# AMS_Slave_Measurement.net
KiCad netlist of a schematic drawn in Altium Designer
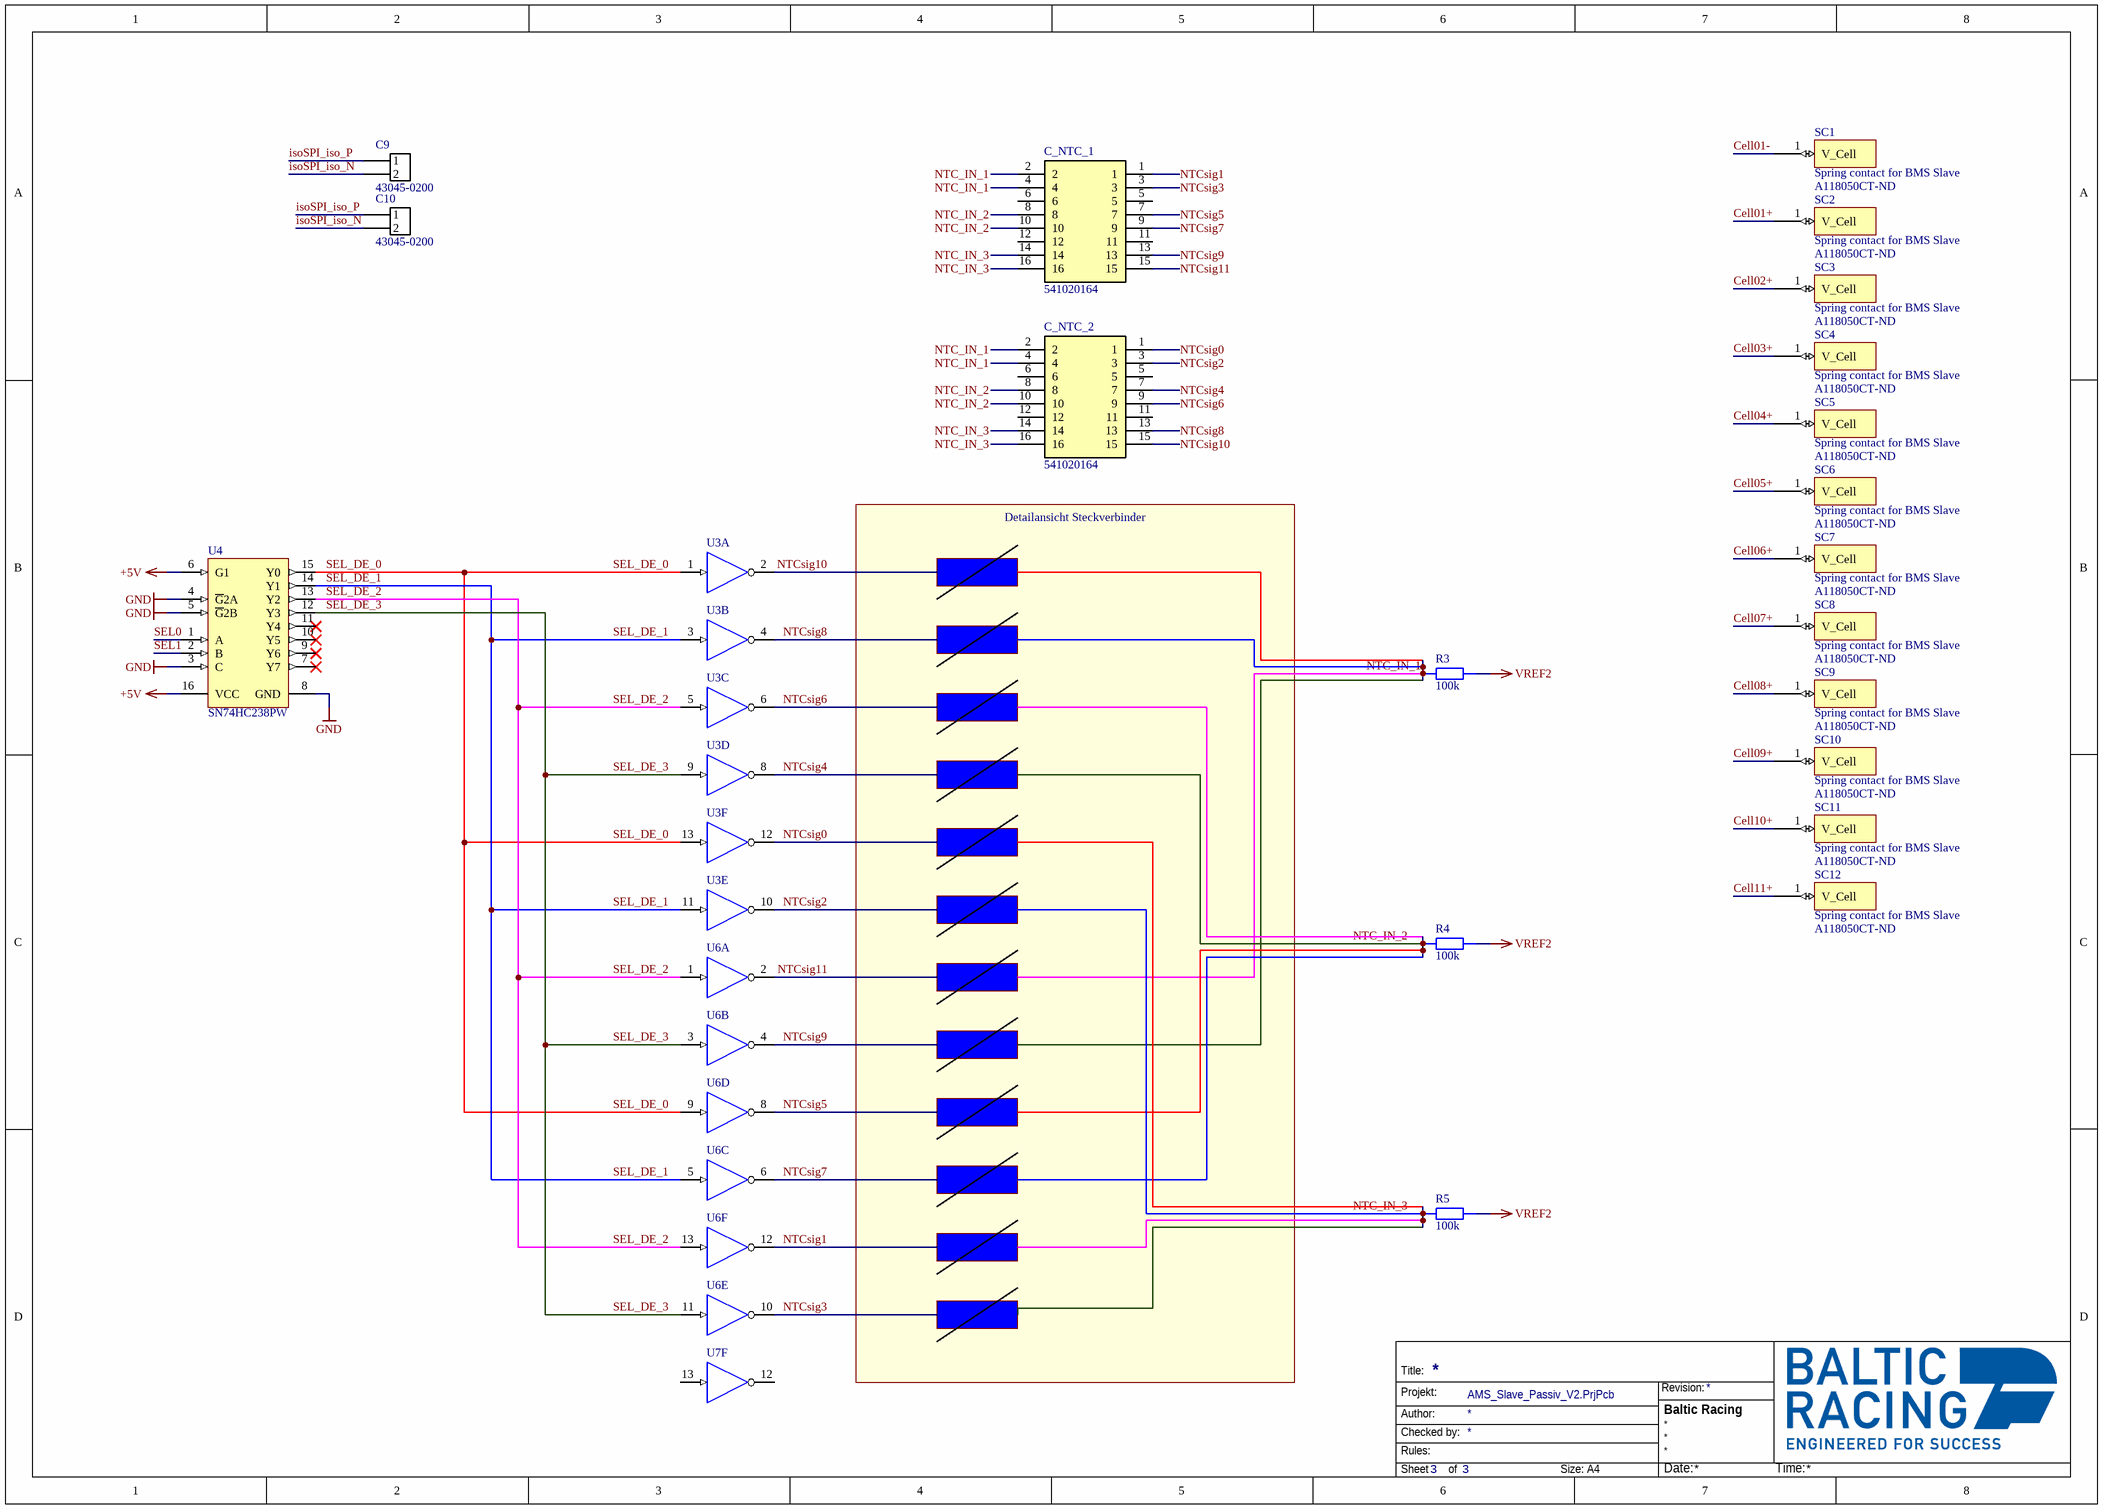
[diagram p0: AMS_Slave_Measurement.SchDoc]

(export (version "E")
  (design (tool "Eeschema 10.0.6"))
  (components
    (comp (ref "C9")
      (value "43045-0200")
      (footprint "43650-0200")
      (description "Molex Micro-Fit 3.0 2-Pin\r\n600V\r\n8.5A")
      (libsource (lib "Standardbauteile") (part "MicroFit3.0 2-Pin"))
    )
    (comp (ref "C10")
      (value "43045-0200")
      (footprint "43650-0200")
      (description "Molex Micro-Fit 3.0 2-Pin\r\n600V\r\n8.5A")
      (libsource (lib "Standardbauteile") (part "MicroFit3.0 2-Pin"))
    )
    (comp (ref "C_NTC_1")
      (value "541020164")
      (footprint "541020164")
      (libsource (lib "libNico") (part "541020164"))
    )
    (comp (ref "C_NTC_2")
      (value "541020164")
      (footprint "541020164")
      (libsource (lib "libNico") (part "541020164"))
    )
    (comp (ref "R3")
      (value "100k")
      (footprint "STACKPOLE CSR0603")
      (description "Resistor with multiple footprints")
      (fields (field (name "Comment") "SMD Resistor"))
      (libsource (lib "Standardbauteile") (part "SMD Resistor"))
    )
    (comp (ref "R4")
      (value "100k")
      (footprint "STACKPOLE CSR0603")
      (description "Resistor with multiple footprints")
      (fields (field (name "Comment") "SMD Resistor"))
      (libsource (lib "Standardbauteile") (part "SMD Resistor"))
    )
    (comp (ref "R5")
      (value "100k")
      (footprint "STACKPOLE CSR0603")
      (description "Resistor with multiple footprints")
      (fields (field (name "Comment") "SMD Resistor"))
      (libsource (lib "Standardbauteile") (part "SMD Resistor"))
    )
    (comp (ref "SC1")
      (value "Spring contact for BMS Slave")
      (footprint "1734300-1 Spring Contact")
      (fields (field (name "SUPPLIER PART NUMBER 1") "A118050CT-ND"))
      (libsource (lib "Integrated_LibraryLukas") (part "1734300-1"))
    )
    (comp (ref "SC2")
      (value "Spring contact for BMS Slave")
      (footprint "1734300-1 Spring Contact")
      (fields (field (name "SUPPLIER PART NUMBER 1") "A118050CT-ND"))
      (libsource (lib "Integrated_LibraryLukas") (part "1734300-1"))
    )
    (comp (ref "SC3")
      (value "Spring contact for BMS Slave")
      (footprint "1734300-1 Spring Contact")
      (fields (field (name "SUPPLIER PART NUMBER 1") "A118050CT-ND"))
      (libsource (lib "Integrated_LibraryLukas") (part "1734300-1"))
    )
    (comp (ref "SC4")
      (value "Spring contact for BMS Slave")
      (footprint "1734300-1 Spring Contact")
      (fields (field (name "SUPPLIER PART NUMBER 1") "A118050CT-ND"))
      (libsource (lib "Integrated_LibraryLukas") (part "1734300-1"))
    )
    (comp (ref "SC5")
      (value "Spring contact for BMS Slave")
      (footprint "1734300-1 Spring Contact")
      (fields (field (name "SUPPLIER PART NUMBER 1") "A118050CT-ND"))
      (libsource (lib "Integrated_LibraryLukas") (part "1734300-1"))
    )
    (comp (ref "SC6")
      (value "Spring contact for BMS Slave")
      (footprint "1734300-1 Spring Contact")
      (fields (field (name "SUPPLIER PART NUMBER 1") "A118050CT-ND"))
      (libsource (lib "Integrated_LibraryLukas") (part "1734300-1"))
    )
    (comp (ref "SC7")
      (value "Spring contact for BMS Slave")
      (footprint "1734300-1 Spring Contact")
      (fields (field (name "SUPPLIER PART NUMBER 1") "A118050CT-ND"))
      (libsource (lib "Integrated_LibraryLukas") (part "1734300-1"))
    )
    (comp (ref "SC8")
      (value "Spring contact for BMS Slave")
      (footprint "1734300-1 Spring Contact")
      (fields (field (name "SUPPLIER PART NUMBER 1") "A118050CT-ND"))
      (libsource (lib "Integrated_LibraryLukas") (part "1734300-1"))
    )
    (comp (ref "SC9")
      (value "Spring contact for BMS Slave")
      (footprint "1734300-1 Spring Contact")
      (fields (field (name "SUPPLIER PART NUMBER 1") "A118050CT-ND"))
      (libsource (lib "Integrated_LibraryLukas") (part "1734300-1"))
    )
    (comp (ref "SC10")
      (value "Spring contact for BMS Slave")
      (footprint "1734300-1 Spring Contact")
      (fields (field (name "SUPPLIER PART NUMBER 1") "A118050CT-ND"))
      (libsource (lib "Integrated_LibraryLukas") (part "1734300-1"))
    )
    (comp (ref "SC11")
      (value "Spring contact for BMS Slave")
      (footprint "1734300-1 Spring Contact")
      (fields (field (name "SUPPLIER PART NUMBER 1") "A118050CT-ND"))
      (libsource (lib "Integrated_LibraryLukas") (part "1734300-1"))
    )
    (comp (ref "SC12")
      (value "Spring contact for BMS Slave")
      (footprint "1734300-1 Spring Contact")
      (fields (field (name "SUPPLIER PART NUMBER 1") "A118050CT-ND"))
      (libsource (lib "Integrated_LibraryLukas") (part "1734300-1"))
    )
    (comp (ref "U3")
      (value "SN74LVC06APWR")
      (footprint "PW0014A_M")
      (description "Hex Inverter Buffers/Drivers With Open-Drain Outputs, PW0014A, LARGE T&R")
      (fields
        (field (name "GENERIC PART NUMBER") "SN74LVC06A")
        (field (name "MANUFACTURER") "Texas Instruments")
      )
      (libsource (lib "Altium Content Vault") (part "TI-CD_SNX4XXXXX05X_X6X-14"))
    )
    (comp (ref "U4")
      (value "SN74HC238PW")
      (footprint "SN74HC238PW Footprint")
      (libsource (lib "Integrated_LibraryLukas_New") (part "SN74HC238PW"))
    )
    (comp (ref "U6")
      (value "SN74LVC06APWR")
      (footprint "PW0014A_M")
      (description "Hex Inverter Buffers/Drivers With Open-Drain Outputs, PW0014A, LARGE T&R")
      (fields
        (field (name "GENERIC PART NUMBER") "SN74LVC06A")
        (field (name "MANUFACTURER") "Texas Instruments")
      )
      (libsource (lib "Altium Content Vault") (part "TI-CD_SNX4XXXXX05X_X6X-14"))
    )
    (comp (ref "U7")
      (value "SN74LVC06APWR")
      (footprint "PW0014A_M")
      (description "Hex Inverter Buffers/Drivers With Open-Drain Outputs, PW0014A, LARGE T&R")
      (fields
        (field (name "GENERIC PART NUMBER") "SN74LVC06A")
        (field (name "MANUFACTURER") "Texas Instruments")
      )
      (libsource (lib "Altium Content Vault") (part "TI-CD_SNX4XXXXX05X_X6X-14"))
    )
  )
  (nets
    (net (code "1") (name "+5V") (class "Default")
      (node (ref "U4") (pin "16") (pinfunction "VCC_16") (pintype "power_in"))
      (node (ref "U4") (pin "6") (pinfunction "G1_6") (pintype "input"))
    )
    (net (code "2") (name "/Cell01+") (class "Default")
      (node (ref "SC2") (pin "1") (pinfunction "V_Cell_1") (pintype "bidirectional"))
    )
    (net (code "3") (name "/Cell01-") (class "Default")
      (node (ref "SC1") (pin "1") (pinfunction "V_Cell_1") (pintype "bidirectional"))
    )
    (net (code "4") (name "/Cell02+") (class "Default")
      (node (ref "SC3") (pin "1") (pinfunction "V_Cell_1") (pintype "bidirectional"))
    )
    (net (code "5") (name "/Cell03+") (class "Default")
      (node (ref "SC4") (pin "1") (pinfunction "V_Cell_1") (pintype "bidirectional"))
    )
    (net (code "6") (name "/Cell04+") (class "Default")
      (node (ref "SC5") (pin "1") (pinfunction "V_Cell_1") (pintype "bidirectional"))
    )
    (net (code "7") (name "/Cell05+") (class "Default")
      (node (ref "SC6") (pin "1") (pinfunction "V_Cell_1") (pintype "bidirectional"))
    )
    (net (code "8") (name "/Cell06+") (class "Default")
      (node (ref "SC7") (pin "1") (pinfunction "V_Cell_1") (pintype "bidirectional"))
    )
    (net (code "9") (name "/Cell07+") (class "Default")
      (node (ref "SC8") (pin "1") (pinfunction "V_Cell_1") (pintype "bidirectional"))
    )
    (net (code "10") (name "/Cell08+") (class "Default")
      (node (ref "SC9") (pin "1") (pinfunction "V_Cell_1") (pintype "bidirectional"))
    )
    (net (code "11") (name "/Cell09+") (class "Default")
      (node (ref "SC10") (pin "1") (pinfunction "V_Cell_1") (pintype "bidirectional"))
    )
    (net (code "12") (name "/Cell10+") (class "Default")
      (node (ref "SC11") (pin "1") (pinfunction "V_Cell_1") (pintype "bidirectional"))
    )
    (net (code "13") (name "/Cell11+") (class "Default")
      (node (ref "SC12") (pin "1") (pinfunction "V_Cell_1") (pintype "bidirectional"))
    )
    (net (code "14") (name "/NTC_IN_1") (class "Default")
      (node (ref "C_NTC_1") (pin "2") (pinfunction "2_2") (pintype "passive"))
      (node (ref "C_NTC_1") (pin "4") (pinfunction "4_4") (pintype "passive"))
      (node (ref "C_NTC_2") (pin "2") (pinfunction "2_2") (pintype "passive"))
      (node (ref "C_NTC_2") (pin "4") (pinfunction "4_4") (pintype "passive"))
      (node (ref "R3") (pin "1") (pinfunction "1_1") (pintype "passive"))
    )
    (net (code "15") (name "/NTC_IN_2") (class "Default")
      (node (ref "C_NTC_1") (pin "10") (pinfunction "10_10") (pintype "passive"))
      (node (ref "C_NTC_1") (pin "8") (pinfunction "8_8") (pintype "passive"))
      (node (ref "C_NTC_2") (pin "10") (pinfunction "10_10") (pintype "passive"))
      (node (ref "C_NTC_2") (pin "8") (pinfunction "8_8") (pintype "passive"))
      (node (ref "R4") (pin "1") (pinfunction "1_1") (pintype "passive"))
    )
    (net (code "16") (name "/NTC_IN_3") (class "Default")
      (node (ref "C_NTC_1") (pin "14") (pinfunction "14_14") (pintype "passive"))
      (node (ref "C_NTC_1") (pin "16") (pinfunction "16_16") (pintype "passive"))
      (node (ref "C_NTC_2") (pin "14") (pinfunction "14_14") (pintype "passive"))
      (node (ref "C_NTC_2") (pin "16") (pinfunction "16_16") (pintype "passive"))
      (node (ref "R5") (pin "1") (pinfunction "1_1") (pintype "passive"))
    )
    (net (code "17") (name "/NTCsig0") (class "Default")
      (node (ref "C_NTC_2") (pin "1") (pinfunction "1_1") (pintype "passive"))
      (node (ref "U3") (pin "12") (pinfunction "~{6Y}_12") (pintype "open_collector"))
    )
    (net (code "18") (name "/NTCsig1") (class "Default")
      (node (ref "C_NTC_1") (pin "1") (pinfunction "1_1") (pintype "passive"))
      (node (ref "U6") (pin "12") (pinfunction "~{6Y}_12") (pintype "open_collector"))
    )
    (net (code "19") (name "/NTCsig2") (class "Default")
      (node (ref "C_NTC_2") (pin "3") (pinfunction "3_3") (pintype "passive"))
      (node (ref "U3") (pin "10") (pinfunction "~{5Y}_10") (pintype "open_collector"))
    )
    (net (code "20") (name "/NTCsig3") (class "Default")
      (node (ref "C_NTC_1") (pin "3") (pinfunction "3_3") (pintype "passive"))
      (node (ref "U6") (pin "10") (pinfunction "~{5Y}_10") (pintype "open_collector"))
    )
    (net (code "21") (name "/NTCsig4") (class "Default")
      (node (ref "C_NTC_2") (pin "7") (pinfunction "7_7") (pintype "passive"))
      (node (ref "U3") (pin "8") (pinfunction "~{4Y}_8") (pintype "open_collector"))
    )
    (net (code "22") (name "/NTCsig5") (class "Default")
      (node (ref "C_NTC_1") (pin "7") (pinfunction "7_7") (pintype "passive"))
      (node (ref "U6") (pin "8") (pinfunction "~{4Y}_8") (pintype "open_collector"))
    )
    (net (code "23") (name "/NTCsig6") (class "Default")
      (node (ref "C_NTC_2") (pin "9") (pinfunction "9_9") (pintype "passive"))
      (node (ref "U3") (pin "6") (pinfunction "~{3Y}_6") (pintype "open_collector"))
    )
    (net (code "24") (name "/NTCsig7") (class "Default")
      (node (ref "C_NTC_1") (pin "9") (pinfunction "9_9") (pintype "passive"))
      (node (ref "U6") (pin "6") (pinfunction "~{3Y}_6") (pintype "open_collector"))
    )
    (net (code "25") (name "/NTCsig8") (class "Default")
      (node (ref "C_NTC_2") (pin "13") (pinfunction "13_13") (pintype "passive"))
      (node (ref "U3") (pin "4") (pinfunction "~{2Y}_4") (pintype "open_collector"))
    )
    (net (code "26") (name "/NTCsig9") (class "Default")
      (node (ref "C_NTC_1") (pin "13") (pinfunction "13_13") (pintype "passive"))
      (node (ref "U6") (pin "4") (pinfunction "~{2Y}_4") (pintype "open_collector"))
    )
    (net (code "27") (name "/NTCsig10") (class "Default")
      (node (ref "C_NTC_2") (pin "15") (pinfunction "15_15") (pintype "passive"))
      (node (ref "U3") (pin "2") (pinfunction "~{1Y}_2") (pintype "open_collector"))
    )
    (net (code "28") (name "/NTCsig11") (class "Default")
      (node (ref "C_NTC_1") (pin "15") (pinfunction "15_15") (pintype "passive"))
      (node (ref "U6") (pin "2") (pinfunction "~{1Y}_2") (pintype "open_collector"))
    )
    (net (code "29") (name "/SEL0") (class "Default")
      (node (ref "U4") (pin "1") (pinfunction "A_1") (pintype "input"))
    )
    (net (code "30") (name "/SEL1") (class "Default")
      (node (ref "U4") (pin "2") (pinfunction "B_2") (pintype "input"))
    )
    (net (code "31") (name "/SEL_DE_0") (class "Default")
      (node (ref "U3") (pin "1") (pinfunction "1A_1") (pintype "input"))
      (node (ref "U3") (pin "13") (pinfunction "6A_13") (pintype "input"))
      (node (ref "U4") (pin "15") (pinfunction "Y0_15") (pintype "output"))
      (node (ref "U6") (pin "9") (pinfunction "4A_9") (pintype "input"))
    )
    (net (code "32") (name "/SEL_DE_1") (class "Default")
      (node (ref "U3") (pin "11") (pinfunction "5A_11") (pintype "input"))
      (node (ref "U3") (pin "3") (pinfunction "2A_3") (pintype "input"))
      (node (ref "U4") (pin "14") (pinfunction "Y1_14") (pintype "output"))
      (node (ref "U6") (pin "5") (pinfunction "3A_5") (pintype "input"))
    )
    (net (code "33") (name "/SEL_DE_2") (class "Default")
      (node (ref "U3") (pin "5") (pinfunction "3A_5") (pintype "input"))
      (node (ref "U4") (pin "13") (pinfunction "Y2_13") (pintype "output"))
      (node (ref "U6") (pin "1") (pinfunction "1A_1") (pintype "input"))
      (node (ref "U6") (pin "13") (pinfunction "6A_13") (pintype "input"))
    )
    (net (code "34") (name "/SEL_DE_3") (class "Default")
      (node (ref "U3") (pin "9") (pinfunction "4A_9") (pintype "input"))
      (node (ref "U4") (pin "12") (pinfunction "Y3_12") (pintype "output"))
      (node (ref "U6") (pin "11") (pinfunction "5A_11") (pintype "input"))
      (node (ref "U6") (pin "3") (pinfunction "2A_3") (pintype "input"))
    )
    (net (code "35") (name "/isoSPI_iso_N") (class "Default")
      (node (ref "C10") (pin "2") (pinfunction "2_2") (pintype "passive"))
      (node (ref "C9") (pin "2") (pinfunction "2_2") (pintype "passive"))
    )
    (net (code "36") (name "/isoSPI_iso_P") (class "Default")
      (node (ref "C10") (pin "1") (pinfunction "1_1") (pintype "passive"))
      (node (ref "C9") (pin "1") (pinfunction "1_1") (pintype "passive"))
    )
    (net (code "37") (name "GND") (class "Default")
      (node (ref "U4") (pin "3") (pinfunction "C_3") (pintype "input"))
      (node (ref "U4") (pin "4") (pinfunction "~{G}2A_4") (pintype "input"))
      (node (ref "U4") (pin "5") (pinfunction "~{G}2B_5") (pintype "input"))
      (node (ref "U4") (pin "8") (pinfunction "GND_8") (pintype "power_in"))
    )
    (net (code "38") (name "VREF2") (class "Default")
      (node (ref "R3") (pin "2") (pinfunction "2_2") (pintype "passive"))
      (node (ref "R4") (pin "2") (pinfunction "2_2") (pintype "passive"))
      (node (ref "R5") (pin "2") (pinfunction "2_2") (pintype "passive"))
    )
    (net (code "39") (name "unconnected-(C_NTC_1-Pad5)") (class "Default")
      (node (ref "C_NTC_1") (pin "5") (pinfunction "5_5") (pintype "passive"))
    )
    (net (code "40") (name "unconnected-(C_NTC_1-Pad6)") (class "Default")
      (node (ref "C_NTC_1") (pin "6") (pinfunction "6_6") (pintype "passive"))
    )
    (net (code "41") (name "unconnected-(C_NTC_1-Pad11)") (class "Default")
      (node (ref "C_NTC_1") (pin "11") (pinfunction "11_11") (pintype "passive"))
    )
    (net (code "42") (name "unconnected-(C_NTC_1-Pad12)") (class "Default")
      (node (ref "C_NTC_1") (pin "12") (pinfunction "12_12") (pintype "passive"))
    )
    (net (code "43") (name "unconnected-(C_NTC_2-Pad5)") (class "Default")
      (node (ref "C_NTC_2") (pin "5") (pinfunction "5_5") (pintype "passive"))
    )
    (net (code "44") (name "unconnected-(C_NTC_2-Pad6)") (class "Default")
      (node (ref "C_NTC_2") (pin "6") (pinfunction "6_6") (pintype "passive"))
    )
    (net (code "45") (name "unconnected-(C_NTC_2-Pad11)") (class "Default")
      (node (ref "C_NTC_2") (pin "11") (pinfunction "11_11") (pintype "passive"))
    )
    (net (code "46") (name "unconnected-(C_NTC_2-Pad12)") (class "Default")
      (node (ref "C_NTC_2") (pin "12") (pinfunction "12_12") (pintype "passive"))
    )
    (net (code "47") (name "unconnected-(U4-Y4-Pad11)") (class "Default")
      (node (ref "U4") (pin "11") (pinfunction "Y4_11") (pintype "output+no_connect"))
    )
    (net (code "48") (name "unconnected-(U4-Y5-Pad10)") (class "Default")
      (node (ref "U4") (pin "10") (pinfunction "Y5_10") (pintype "output+no_connect"))
    )
    (net (code "49") (name "unconnected-(U4-Y6-Pad9)") (class "Default")
      (node (ref "U4") (pin "9") (pinfunction "Y6_9") (pintype "output+no_connect"))
    )
    (net (code "50") (name "unconnected-(U4-Y7-Pad7)") (class "Default")
      (node (ref "U4") (pin "7") (pinfunction "Y7_7") (pintype "output+no_connect"))
    )
    (net (code "51") (name "unconnected-(U7F-6A-Pad13)") (class "Default")
      (node (ref "U7") (pin "13") (pinfunction "6A_13") (pintype "input"))
    )
    (net (code "52") (name "unconnected-(U7F-~{6Y}-Pad12)") (class "Default")
      (node (ref "U7") (pin "12") (pinfunction "~{6Y}_12") (pintype "open_collector"))
    )
  )
)
